# RECEPTOR_AIS_DEMOD_R00.net
KiCad netlist of a schematic drawn in Altium Designer
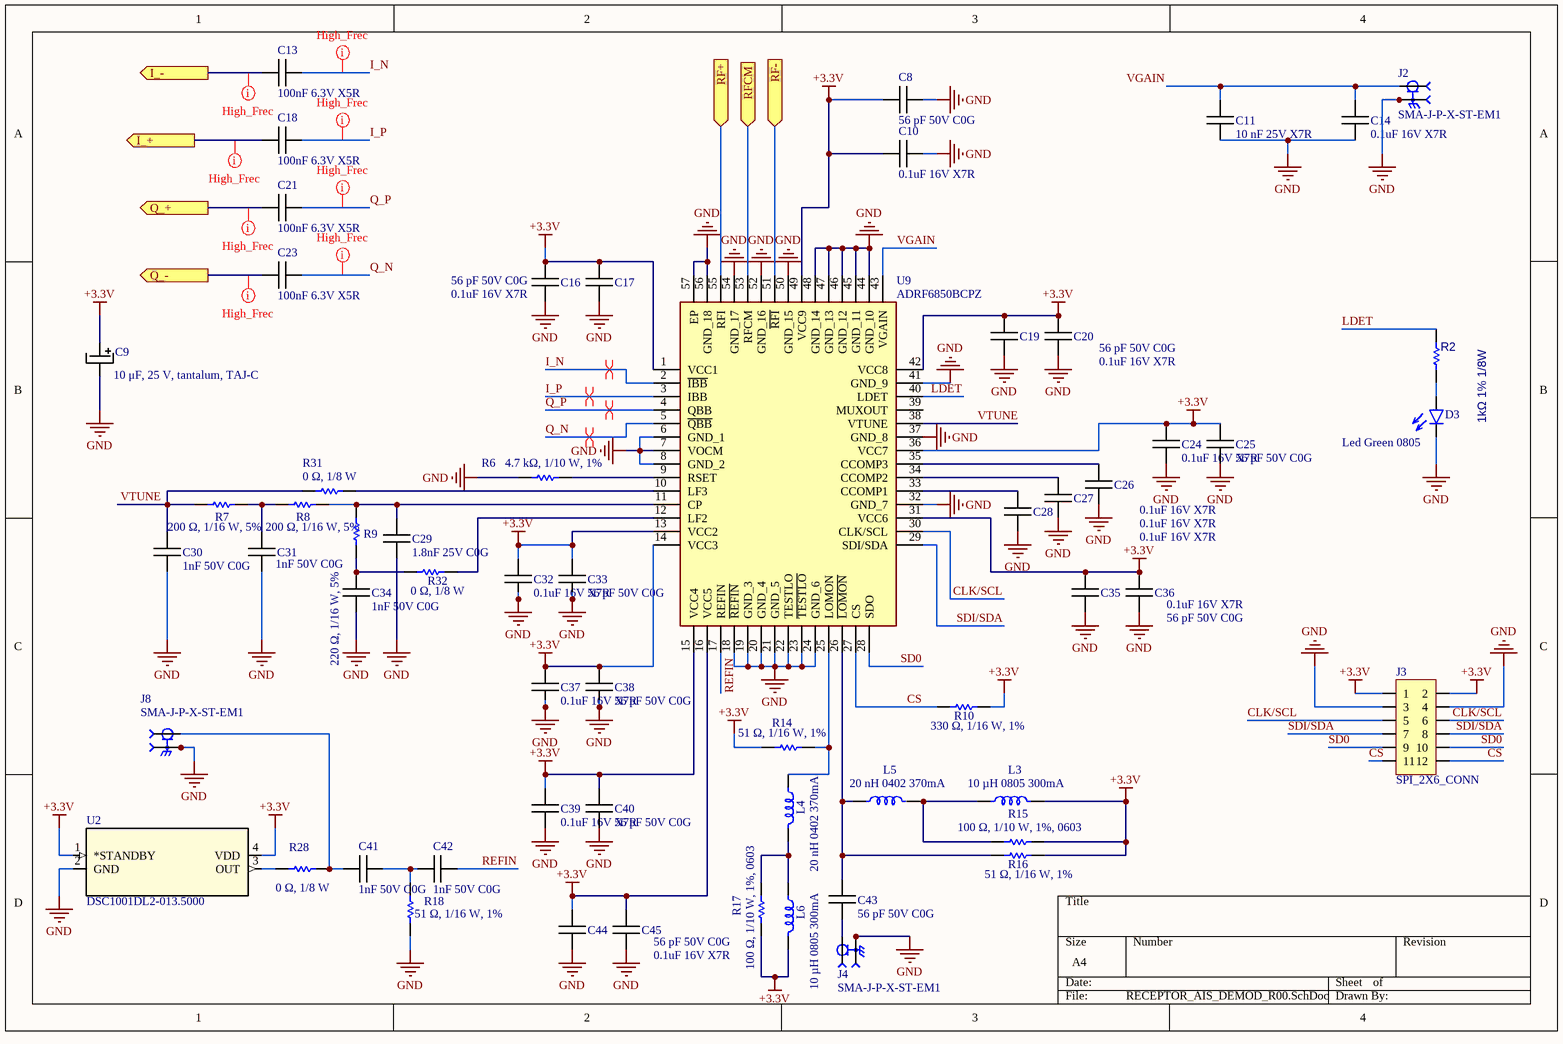
[diagram p0: RECEPTOR_AIS_DEMOD_R00.SchDoc]

(export (version "E")
  (design (tool "Eeschema 10.0.6"))
  (components
    (comp (ref "C8")
      (value "56 pF 50V C0G")
      (footprint "C_0603")
      (description "56 pF ±5% 50V Ceramic Capacitor C0G, NP0 0603 (1608 Metric)")
      (libsource (lib "RECEPTOR_AIS_R00") (part "Capacitor NP"))
    )
    (comp (ref "C9")
      (value "10 μF, 25 V, tantalum, TAJ-C")
      (footprint "TAJC_AVX-M")
      (description "10 µF Molded Tantalum Capacitors 25 V 2312 (6032 Metric) 1.8Ohm")
      (libsource (lib "RECEPTOR_AIS_R00") (part "Capacitor Pol"))
    )
    (comp (ref "C10")
      (value "0.1uF 16V X7R")
      (footprint "C_0603")
      (description "0.1 µF ±10% 16V Ceramic Capacitor X7R 0603 (1608 Metric)")
      (libsource (lib "RECEPTOR_AIS_R00") (part "Capacitor NP"))
    )
    (comp (ref "C11")
      (value "10 nF 25V X7R")
      (footprint "C_0603")
      (description "10000 pF ±10% 25V Ceramic Capacitor X7R 0603 (1608 Metric)")
      (libsource (lib "RECEPTOR_AIS_R00") (part "Capacitor NP"))
    )
    (comp (ref "C13")
      (value "100nF 6.3V X5R")
      (footprint "C_0603")
      (description "0.1 µF ±10% 6.3V Ceramic Capacitor X5R 0603 (1608 Metric)")
      (libsource (lib "RECEPTOR_AIS_R00") (part "Capacitor NP"))
    )
    (comp (ref "C14")
      (value "0.1uF 16V X7R")
      (footprint "C_0603")
      (description "0.1 µF ±10% 16V Ceramic Capacitor X7R 0603 (1608 Metric)")
      (libsource (lib "RECEPTOR_AIS_R00") (part "Capacitor NP"))
    )
    (comp (ref "C16")
      (value "0.1uF 16V X7R")
      (footprint "C_0603")
      (description "0.1 µF ±10% 16V Ceramic Capacitor X7R 0603 (1608 Metric)")
      (libsource (lib "RECEPTOR_AIS_R00") (part "Capacitor NP"))
    )
    (comp (ref "C17")
      (value "56 pF 50V C0G")
      (footprint "C_0603")
      (description "56 pF ±5% 50V Ceramic Capacitor C0G, NP0 0603 (1608 Metric)")
      (libsource (lib "RECEPTOR_AIS_R00") (part "Capacitor NP"))
    )
    (comp (ref "C18")
      (value "100nF 6.3V X5R")
      (footprint "C_0603")
      (description "0.1 µF ±10% 6.3V Ceramic Capacitor X5R 0603 (1608 Metric)")
      (libsource (lib "RECEPTOR_AIS_R00") (part "Capacitor NP"))
    )
    (comp (ref "C19")
      (value "0.1uF 16V X7R")
      (footprint "C_0603")
      (description "0.1 µF ±10% 16V Ceramic Capacitor X7R 0603 (1608 Metric)")
      (libsource (lib "RECEPTOR_AIS_R00") (part "Capacitor NP"))
    )
    (comp (ref "C20")
      (value "56 pF 50V C0G")
      (footprint "C_0603")
      (description "56 pF ±5% 50V Ceramic Capacitor C0G, NP0 0603 (1608 Metric)")
      (libsource (lib "RECEPTOR_AIS_R00") (part "Capacitor NP"))
    )
    (comp (ref "C21")
      (value "100nF 6.3V X5R")
      (footprint "C_0603")
      (description "0.1 µF ±10% 6.3V Ceramic Capacitor X5R 0603 (1608 Metric)")
      (libsource (lib "RECEPTOR_AIS_R00") (part "Capacitor NP"))
    )
    (comp (ref "C23")
      (value "100nF 6.3V X5R")
      (footprint "C_0603")
      (description "0.1 µF ±10% 6.3V Ceramic Capacitor X5R 0603 (1608 Metric)")
      (libsource (lib "RECEPTOR_AIS_R00") (part "Capacitor NP"))
    )
    (comp (ref "C24")
      (value "0.1uF 16V X7R")
      (footprint "C_0603")
      (description "0.1 µF ±10% 16V Ceramic Capacitor X7R 0603 (1608 Metric)")
      (libsource (lib "RECEPTOR_AIS_R00") (part "Capacitor NP"))
    )
    (comp (ref "C25")
      (value "56 pF 50V C0G")
      (footprint "C_0603")
      (description "56 pF ±5% 50V Ceramic Capacitor C0G, NP0 0603 (1608 Metric)")
      (libsource (lib "RECEPTOR_AIS_R00") (part "Capacitor NP"))
    )
    (comp (ref "C26")
      (value "0.1uF 16V X7R")
      (footprint "C_0603")
      (description "0.1 µF ±10% 16V Ceramic Capacitor X7R 0603 (1608 Metric)")
      (libsource (lib "RECEPTOR_AIS_R00") (part "Capacitor NP"))
    )
    (comp (ref "C27")
      (value "0.1uF 16V X7R")
      (footprint "C_0603")
      (description "0.1 µF ±10% 16V Ceramic Capacitor X7R 0603 (1608 Metric)")
      (libsource (lib "RECEPTOR_AIS_R00") (part "Capacitor NP"))
    )
    (comp (ref "C28")
      (value "0.1uF 16V X7R")
      (footprint "C_0603")
      (description "0.1 µF ±10% 16V Ceramic Capacitor X7R 0603 (1608 Metric)")
      (libsource (lib "RECEPTOR_AIS_R00") (part "Capacitor NP"))
    )
    (comp (ref "C29")
      (value "1.8nF 25V C0G")
      (footprint "C_0603")
      (description "1800 pF ±5% 25V Ceramic Capacitor C0G, NP0 0603 (1608 Metric)")
      (libsource (lib "RECEPTOR_AIS_R00") (part "Capacitor NP"))
    )
    (comp (ref "C30")
      (value "1nF 50V C0G")
      (footprint "C_0603")
      (description "1000 pF ±5% 50V Ceramic Capacitor C0G, NP0 0603 (1608 Metric)")
      (libsource (lib "RECEPTOR_AIS_R00") (part "Capacitor NP"))
    )
    (comp (ref "C31")
      (value "1nF 50V C0G")
      (footprint "C_0603")
      (description "1000 pF ±5% 50V Ceramic Capacitor C0G, NP0 0603 (1608 Metric)")
      (libsource (lib "RECEPTOR_AIS_R00") (part "Capacitor NP"))
    )
    (comp (ref "C32")
      (value "0.1uF 16V X7R")
      (footprint "C_0603")
      (description "0.1 µF ±10% 16V Ceramic Capacitor X7R 0603 (1608 Metric)")
      (libsource (lib "RECEPTOR_AIS_R00") (part "Capacitor NP"))
    )
    (comp (ref "C33")
      (value "56 pF 50V C0G")
      (footprint "C_0603")
      (description "56 pF ±5% 50V Ceramic Capacitor C0G, NP0 0603 (1608 Metric)")
      (libsource (lib "RECEPTOR_AIS_R00") (part "Capacitor NP"))
    )
    (comp (ref "C34")
      (value "1nF 50V C0G")
      (footprint "C_0603")
      (description "1000 pF ±5% 50V Ceramic Capacitor C0G, NP0 0603 (1608 Metric)")
      (libsource (lib "RECEPTOR_AIS_R00") (part "Capacitor NP"))
    )
    (comp (ref "C35")
      (value "0.1uF 16V X7R")
      (footprint "C_0603")
      (description "0.1 µF ±10% 16V Ceramic Capacitor X7R 0603 (1608 Metric)")
      (libsource (lib "RECEPTOR_AIS_R00") (part "Capacitor NP"))
    )
    (comp (ref "C36")
      (value "56 pF 50V C0G")
      (footprint "C_0603")
      (description "56 pF ±5% 50V Ceramic Capacitor C0G, NP0 0603 (1608 Metric)")
      (libsource (lib "RECEPTOR_AIS_R00") (part "Capacitor NP"))
    )
    (comp (ref "C37")
      (value "0.1uF 16V X7R")
      (footprint "C_0603")
      (description "0.1 µF ±10% 16V Ceramic Capacitor X7R 0603 (1608 Metric)")
      (libsource (lib "RECEPTOR_AIS_R00") (part "Capacitor NP"))
    )
    (comp (ref "C38")
      (value "56 pF 50V C0G")
      (footprint "C_0603")
      (description "56 pF ±5% 50V Ceramic Capacitor C0G, NP0 0603 (1608 Metric)")
      (libsource (lib "RECEPTOR_AIS_R00") (part "Capacitor NP"))
    )
    (comp (ref "C39")
      (value "0.1uF 16V X7R")
      (footprint "C_0603")
      (description "0.1 µF ±10% 16V Ceramic Capacitor X7R 0603 (1608 Metric)")
      (libsource (lib "RECEPTOR_AIS_R00") (part "Capacitor NP"))
    )
    (comp (ref "C40")
      (value "56 pF 50V C0G")
      (footprint "C_0603")
      (description "56 pF ±5% 50V Ceramic Capacitor C0G, NP0 0603 (1608 Metric)")
      (libsource (lib "RECEPTOR_AIS_R00") (part "Capacitor NP"))
    )
    (comp (ref "C41")
      (value "1nF 50V C0G")
      (footprint "C_0603")
      (description "1000 pF ±5% 50V Ceramic Capacitor C0G, NP0 0603 (1608 Metric)")
      (libsource (lib "RECEPTOR_AIS_R00") (part "Capacitor NP"))
    )
    (comp (ref "C42")
      (value "1nF 50V C0G")
      (footprint "C_0603")
      (description "1000 pF ±5% 50V Ceramic Capacitor C0G, NP0 0603 (1608 Metric)")
      (libsource (lib "RECEPTOR_AIS_R00") (part "Capacitor NP"))
    )
    (comp (ref "C43")
      (value "56 pF 50V C0G")
      (footprint "C_0603")
      (description "56 pF ±5% 50V Ceramic Capacitor C0G, NP0 0603 (1608 Metric)")
      (libsource (lib "RECEPTOR_AIS_R00") (part "Capacitor NP"))
    )
    (comp (ref "C44")
      (value "0.1uF 16V X7R")
      (footprint "C_0603")
      (description "0.1 µF ±10% 16V Ceramic Capacitor X7R 0603 (1608 Metric)")
      (libsource (lib "RECEPTOR_AIS_R00") (part "Capacitor NP"))
    )
    (comp (ref "C45")
      (value "56 pF 50V C0G")
      (footprint "C_0603")
      (description "56 pF ±5% 50V Ceramic Capacitor C0G, NP0 0603 (1608 Metric)")
      (libsource (lib "RECEPTOR_AIS_R00") (part "Capacitor NP"))
    )
    (comp (ref "D3")
      (value "Led Green 0805")
      (footprint "LED_0805")
      (description "Green 569nm LED Indication - Discrete 2.1V 0805 (2012 Metric)")
      (libsource (lib "RECEPTOR_AIS_R00") (part "Led"))
    )
    (comp (ref "J2")
      (value "SMA-J-P-X-ST-EM1")
      (footprint "CONN_SMA-J-P-H-ST-EM1_SAI")
      (description "SMA Connector Jack, Female Socket 50 Ohms Board Edge, Cutout; Surface Mount Solder")
      (fields (field (name "MF") "Samtec") (field (name "MP") "SMA-J-P-H-ST-EM3"))
      (libsource (lib "RECEPTOR_AIS_R00") (part "SMA-J-P-X-ST-EM1"))
    )
    (comp (ref "J3")
      (value "SPI_2X6_CONN")
      (footprint "Pin_Header_2x6")
      (libsource (lib "RECEPTOR_AIS_R00") (part "SPI_2x6Pin_Connection"))
    )
    (comp (ref "J4")
      (value "SMA-J-P-X-ST-EM1")
      (footprint "CONN_SMA-J-P-H-ST-EM1_SAI")
      (description "SMA Connector Jack, Female Socket 50 Ohms Board Edge, Cutout; Surface Mount Solder")
      (fields (field (name "MF") "Samtec") (field (name "MP") "SMA-J-P-H-ST-EM3"))
      (libsource (lib "RECEPTOR_AIS_R00") (part "SMA-J-P-X-ST-EM1"))
    )
    (comp (ref "J8")
      (value "SMA-J-P-X-ST-EM1")
      (footprint "CONN_SMA-J-P-H-ST-EM1_SAI")
      (description "SMA Connector Jack, Female Socket 50 Ohms Board Edge, Cutout; Surface Mount Solder")
      (fields (field (name "MF") "Samtec") (field (name "MP") "SMA-J-P-H-ST-EM3"))
      (libsource (lib "RECEPTOR_AIS_R00") (part "SMA-J-P-X-ST-EM1"))
    )
    (comp (ref "L3")
      (value "10 µH 0805 300mA")
      (footprint "L_0603")
      (description "LQM18DN100M70L - 10 µH Shielded Multilayer Inductor 300 mA 1.365Ohm Max 0603 (1608 Metric)")
      (libsource (lib "RECEPTOR_AIS_R00") (part "IND"))
    )
    (comp (ref "L4")
      (value "20 nH 0402 370mA")
      (footprint "L_0402")
      (description "LQW15AN20NJ00D - 20 nH Unshielded Wirewound Inductor 370 mA 270mOhm Max 0402 (1005 Metric)")
      (libsource (lib "RECEPTOR_AIS_R00") (part "IND"))
    )
    (comp (ref "L5")
      (value "20 nH 0402 370mA")
      (footprint "L_0402")
      (description "LQW15AN20NJ00D - 20 nH Unshielded Wirewound Inductor 370 mA 270mOhm Max 0402 (1005 Metric)")
      (libsource (lib "RECEPTOR_AIS_R00") (part "IND"))
    )
    (comp (ref "L6")
      (value "10 µH 0805 300mA")
      (footprint "L_0603")
      (description "LQM18DN100M70L - 10 µH Shielded Multilayer Inductor 300 mA 1.365Ohm Max 0603 (1608 Metric)")
      (libsource (lib "RECEPTOR_AIS_R00") (part "IND"))
    )
    (comp (ref "R2")
      (value "1kΩ 1% 1/8W")
      (footprint "R_0603")
      (description "100 Ohms ±0.1% 1/8W Chip Resistor 0603 (1608 Metric) Thin Film")
      (libsource (lib "RECEPTOR_AIS_R00") (part "Res1"))
    )
    (comp (ref "R6")
      (value "4.7 kΩ, 1/10 W, 1%")
      (footprint "R_0603")
      (description "4.7 kOhms ±1% 0.1W, 1/10W Chip Resistor 0603 (1608 Metric) Moisture Resistant Thick Film")
      (libsource (lib "RECEPTOR_AIS_R00") (part "Res1"))
    )
    (comp (ref "R7")
      (value "200 Ω, 1/16 W, 5%")
      (footprint "R_0603")
      (description "200 Ohms ±5% 0.1W, 1/10W Chip Resistor 0603 (1608 Metric) Moisture Resistant Thick Film")
      (libsource (lib "RECEPTOR_AIS_R00") (part "Res1"))
    )
    (comp (ref "R8")
      (value "200 Ω, 1/16 W, 5%")
      (footprint "R_0603")
      (description "200 Ohms ±5% 0.1W, 1/10W Chip Resistor 0603 (1608 Metric) Moisture Resistant Thick Film")
      (libsource (lib "RECEPTOR_AIS_R00") (part "Res1"))
    )
    (comp (ref "R9")
      (value "220 Ω, 1/16 W, 5%")
      (footprint "R_0603")
      (description "220 Ohms ±5% 0.1W, 1/10W Chip Resistor 0603 (1608 Metric) Moisture Resistant Thick Film")
      (libsource (lib "RECEPTOR_AIS_R00") (part "Res1"))
    )
    (comp (ref "R10")
      (value "330 Ω, 1/16 W, 1%")
      (footprint "R_0805")
      (description "330 Ohms ±1% 0.125W, 1/8W Chip Resistor 0805 (2012 Metric) Moisture Resistant Thick Film")
      (libsource (lib "RECEPTOR_AIS_R00") (part "Res1"))
    )
    (comp (ref "R14")
      (value "51 Ω, 1/16 W, 1%")
      (footprint "R_0805")
      (libsource (lib "RECEPTOR_AIS_R00") (part "Res1"))
    )
    (comp (ref "R15")
      (value "100 Ω, 1/10 W, 1%, 0603")
      (footprint "R_0603")
      (description "100 Ohms ±1% 0.1W, 1/10W Chip Resistor 0603 (1608 Metric) Moisture Resistant Thick Film")
      (libsource (lib "RECEPTOR_AIS_R00") (part "Res1"))
    )
    (comp (ref "R16")
      (value "51 Ω, 1/16 W, 1%")
      (footprint "R_0805")
      (libsource (lib "RECEPTOR_AIS_R00") (part "Res1"))
    )
    (comp (ref "R17")
      (value "100 Ω, 1/10 W, 1%, 0603")
      (footprint "R_0603")
      (description "100 Ohms ±1% 0.1W, 1/10W Chip Resistor 0603 (1608 Metric) Moisture Resistant Thick Film")
      (libsource (lib "RECEPTOR_AIS_R00") (part "Res1"))
    )
    (comp (ref "R18")
      (value "51 Ω, 1/16 W, 1%")
      (footprint "R_0805")
      (libsource (lib "RECEPTOR_AIS_R00") (part "Res1"))
    )
    (comp (ref "R28")
      (value "0 Ω, 1/8 W")
      (footprint "R_0603")
      (libsource (lib "RECEPTOR_AIS_R00") (part "Res1"))
    )
    (comp (ref "R31")
      (value "0 Ω, 1/8 W")
      (footprint "R_0603")
      (libsource (lib "RECEPTOR_AIS_R00") (part "Res1"))
    )
    (comp (ref "R32")
      (value "0 Ω, 1/8 W")
      (footprint "R_0603")
      (libsource (lib "RECEPTOR_AIS_R00") (part "Res1"))
    )
    (comp (ref "U2")
      (value "DSC1001DL2-013.5000")
      (footprint "CDFN4_2P5X2_MCH")
      (description "13.5 MHz XO (Standard) CMOS Oscillator 1.7V ~ 3.6V Standby (Power Down) 4-VDFN")
      (fields (field (name "COPYRIGHT") "Copyright (C) 2026 Ultra Librarian. All rights reserved."))
      (libsource (lib "RECEPTOR_AIS_R00") (part "DSC1001DL2-013.5000"))
    )
    (comp (ref "U9")
      (value "ADRF6850BCPZ")
      (footprint "QFN50P800X800X100-57N-D")
      (description "ADRF6850BCPZ, Demodulator Quadrature 250MHz 3.15  3.45 V 56-Pin LFCSP VQ")
      (fields (field (name "MOUSER PART NUMBER") "584-ADRF6850BCPZ"))
      (libsource (lib "RECEPTOR_AIS_R00") (part "ADRF6850BCPZ"))
    )
  )
  (nets
    (net (code "1") (name "+3.3V") (class "Default")
      (node (ref "C10") (pin "1") (pinfunction "1_1") (pintype "passive"))
      (node (ref "C16") (pin "1") (pinfunction "1_1") (pintype "passive"))
      (node (ref "C17") (pin "1") (pinfunction "1_1") (pintype "passive"))
      (node (ref "C19") (pin "1") (pinfunction "1_1") (pintype "passive"))
      (node (ref "C20") (pin "1") (pinfunction "1_1") (pintype "passive"))
      (node (ref "C24") (pin "1") (pinfunction "1_1") (pintype "passive"))
      (node (ref "C25") (pin "1") (pinfunction "1_1") (pintype "passive"))
      (node (ref "C32") (pin "1") (pinfunction "1_1") (pintype "passive"))
      (node (ref "C33") (pin "1") (pinfunction "1_1") (pintype "passive"))
      (node (ref "C35") (pin "1") (pinfunction "1_1") (pintype "passive"))
      (node (ref "C36") (pin "1") (pinfunction "1_1") (pintype "passive"))
      (node (ref "C37") (pin "1") (pinfunction "1_1") (pintype "passive"))
      (node (ref "C38") (pin "1") (pinfunction "1_1") (pintype "passive"))
      (node (ref "C39") (pin "1") (pinfunction "1_1") (pintype "passive"))
      (node (ref "C40") (pin "1") (pinfunction "1_1") (pintype "passive"))
      (node (ref "C44") (pin "1") (pinfunction "1_1") (pintype "passive"))
      (node (ref "C45") (pin "1") (pinfunction "1_1") (pintype "passive"))
      (node (ref "C8") (pin "1") (pinfunction "1_1") (pintype "passive"))
      (node (ref "C9") (pin "1") (pinfunction "1_1") (pintype "power_in"))
      (node (ref "J3") (pin "1") (pinfunction "1_1") (pintype "passive"))
      (node (ref "J3") (pin "2") (pinfunction "2_2") (pintype "passive"))
      (node (ref "L3") (pin "2") (pinfunction "2_2") (pintype "passive"))
      (node (ref "L6") (pin "2") (pinfunction "2_2") (pintype "passive"))
      (node (ref "R10") (pin "2") (pinfunction "2_2") (pintype "passive"))
      (node (ref "R14") (pin "2") (pinfunction "2_2") (pintype "passive"))
      (node (ref "R15") (pin "2") (pinfunction "2_2") (pintype "passive"))
      (node (ref "R16") (pin "2") (pinfunction "2_2") (pintype "passive"))
      (node (ref "R17") (pin "2") (pinfunction "2_2") (pintype "passive"))
      (node (ref "U2") (pin "1") (pinfunction "*STANDBY_1") (pintype "input"))
      (node (ref "U2") (pin "4") (pinfunction "VDD_4") (pintype "power_in"))
      (node (ref "U9") (pin "1") (pinfunction "VCC1_1") (pintype "passive"))
      (node (ref "U9") (pin "13") (pinfunction "VCC2_13") (pintype "passive"))
      (node (ref "U9") (pin "14") (pinfunction "VCC3_14") (pintype "passive"))
      (node (ref "U9") (pin "15") (pinfunction "VCC4_15") (pintype "passive"))
      (node (ref "U9") (pin "16") (pinfunction "VCC5_16") (pintype "passive"))
      (node (ref "U9") (pin "31") (pinfunction "VCC6_31") (pintype "passive"))
      (node (ref "U9") (pin "36") (pinfunction "VCC7_36") (pintype "passive"))
      (node (ref "U9") (pin "42") (pinfunction "VCC8_42") (pintype "passive"))
      (node (ref "U9") (pin "49") (pinfunction "VCC9_49") (pintype "passive"))
    )
    (net (code "2") (name "/CLK{slash}SCL") (class "Default")
      (node (ref "J3") (pin "5") (pinfunction "5_5") (pintype "passive"))
      (node (ref "J3") (pin "6") (pinfunction "6_6") (pintype "passive"))
      (node (ref "U9") (pin "30") (pinfunction "CLK/SCL_30") (pintype "passive"))
    )
    (net (code "3") (name "/CS") (class "Default")
      (node (ref "J3") (pin "11") (pinfunction "11_11") (pintype "power_in"))
      (node (ref "J3") (pin "12") (pinfunction "12_12") (pintype "power_in"))
      (node (ref "R10") (pin "1") (pinfunction "1_1") (pintype "passive"))
      (node (ref "U9") (pin "27") (pinfunction "CS_27") (pintype "passive"))
    )
    (net (code "4") (name "/I_+") (class "Default")
      (node (ref "C18") (pin "2") (pinfunction "2_2") (pintype "passive"))
    )
    (net (code "5") (name "/I_-") (class "Default")
      (node (ref "C13") (pin "2") (pinfunction "2_2") (pintype "passive"))
    )
    (net (code "6") (name "/I_N") (class "Default")
      (node (ref "C13") (pin "1") (pinfunction "1_1") (pintype "passive"))
      (node (ref "U9") (pin "2") (pinfunction "~{IBB}_2") (pintype "passive"))
    )
    (net (code "7") (name "/I_P") (class "Default")
      (node (ref "C18") (pin "1") (pinfunction "1_1") (pintype "passive"))
      (node (ref "U9") (pin "3") (pinfunction "IBB_3") (pintype "passive"))
    )
    (net (code "8") (name "/LDET") (class "Default")
      (node (ref "R2") (pin "2") (pinfunction "2_2") (pintype "passive"))
      (node (ref "U9") (pin "40") (pinfunction "LDET_40") (pintype "passive"))
    )
    (net (code "9") (name "/Q_+") (class "Default")
      (node (ref "C21") (pin "2") (pinfunction "2_2") (pintype "passive"))
    )
    (net (code "10") (name "/Q_-") (class "Default")
      (node (ref "C23") (pin "2") (pinfunction "2_2") (pintype "passive"))
    )
    (net (code "11") (name "/Q_N") (class "Default")
      (node (ref "C23") (pin "1") (pinfunction "1_1") (pintype "passive"))
      (node (ref "U9") (pin "5") (pinfunction "~{QBB}_5") (pintype "passive"))
    )
    (net (code "12") (name "/Q_P") (class "Default")
      (node (ref "C21") (pin "1") (pinfunction "1_1") (pintype "passive"))
      (node (ref "U9") (pin "4") (pinfunction "QBB_4") (pintype "passive"))
    )
    (net (code "13") (name "/REFIN") (class "Default")
      (node (ref "C42") (pin "1") (pinfunction "1_1") (pintype "passive"))
      (node (ref "U9") (pin "17") (pinfunction "REFIN_17") (pintype "passive"))
    )
    (net (code "14") (name "/RF+") (class "Default")
      (node (ref "U9") (pin "55") (pinfunction "RFI_55") (pintype "passive"))
    )
    (net (code "15") (name "/RF-") (class "Default")
      (node (ref "U9") (pin "51") (pinfunction "~{RFI}_51") (pintype "passive"))
    )
    (net (code "16") (name "/RFCM") (class "Default")
      (node (ref "U9") (pin "53") (pinfunction "RFCM_53") (pintype "passive"))
    )
    (net (code "17") (name "/SD0") (class "Default")
      (node (ref "J3") (pin "10") (pinfunction "10_10") (pintype "power_in"))
      (node (ref "J3") (pin "9") (pinfunction "9_9") (pintype "power_in"))
      (node (ref "U9") (pin "28") (pinfunction "SDO_28") (pintype "passive"))
    )
    (net (code "18") (name "/SDI{slash}SDA") (class "Default")
      (node (ref "J3") (pin "7") (pinfunction "7_7") (pintype "power_in"))
      (node (ref "J3") (pin "8") (pinfunction "8_8") (pintype "power_in"))
      (node (ref "U9") (pin "29") (pinfunction "SDI/SDA_29") (pintype "passive"))
    )
    (net (code "19") (name "/VGAIN") (class "Default")
      (node (ref "C11") (pin "1") (pinfunction "1_1") (pintype "passive"))
      (node (ref "C14") (pin "1") (pinfunction "1_1") (pintype "passive"))
      (node (ref "J2") (pin "1") (pinfunction "1_1") (pintype "passive"))
      (node (ref "U9") (pin "43") (pinfunction "VGAIN_43") (pintype "passive"))
    )
    (net (code "20") (name "/VTUNE") (class "Default")
      (node (ref "C30") (pin "1") (pinfunction "1_1") (pintype "passive"))
      (node (ref "R31") (pin "1") (pinfunction "1_1") (pintype "passive"))
      (node (ref "R7") (pin "2") (pinfunction "2_2") (pintype "passive"))
      (node (ref "U9") (pin "38") (pinfunction "VTUNE_38") (pintype "passive"))
    )
    (net (code "21") (name "GND") (class "Default")
      (node (ref "C10") (pin "2") (pinfunction "2_2") (pintype "passive"))
      (node (ref "C11") (pin "2") (pinfunction "2_2") (pintype "passive"))
      (node (ref "C14") (pin "2") (pinfunction "2_2") (pintype "passive"))
      (node (ref "C16") (pin "2") (pinfunction "2_2") (pintype "passive"))
      (node (ref "C17") (pin "2") (pinfunction "2_2") (pintype "passive"))
      (node (ref "C19") (pin "2") (pinfunction "2_2") (pintype "passive"))
      (node (ref "C20") (pin "2") (pinfunction "2_2") (pintype "passive"))
      (node (ref "C24") (pin "2") (pinfunction "2_2") (pintype "passive"))
      (node (ref "C25") (pin "2") (pinfunction "2_2") (pintype "passive"))
      (node (ref "C26") (pin "2") (pinfunction "2_2") (pintype "passive"))
      (node (ref "C27") (pin "2") (pinfunction "2_2") (pintype "passive"))
      (node (ref "C28") (pin "2") (pinfunction "2_2") (pintype "passive"))
      (node (ref "C29") (pin "2") (pinfunction "2_2") (pintype "passive"))
      (node (ref "C30") (pin "2") (pinfunction "2_2") (pintype "passive"))
      (node (ref "C31") (pin "2") (pinfunction "2_2") (pintype "passive"))
      (node (ref "C32") (pin "2") (pinfunction "2_2") (pintype "passive"))
      (node (ref "C33") (pin "2") (pinfunction "2_2") (pintype "passive"))
      (node (ref "C34") (pin "2") (pinfunction "2_2") (pintype "passive"))
      (node (ref "C35") (pin "2") (pinfunction "2_2") (pintype "passive"))
      (node (ref "C36") (pin "2") (pinfunction "2_2") (pintype "passive"))
      (node (ref "C37") (pin "2") (pinfunction "2_2") (pintype "passive"))
      (node (ref "C38") (pin "2") (pinfunction "2_2") (pintype "passive"))
      (node (ref "C39") (pin "2") (pinfunction "2_2") (pintype "passive"))
      (node (ref "C40") (pin "2") (pinfunction "2_2") (pintype "passive"))
      (node (ref "C44") (pin "2") (pinfunction "2_2") (pintype "passive"))
      (node (ref "C45") (pin "2") (pinfunction "2_2") (pintype "passive"))
      (node (ref "C8") (pin "2") (pinfunction "2_2") (pintype "passive"))
      (node (ref "C9") (pin "2") (pinfunction "2_2") (pintype "power_in"))
      (node (ref "D3") (pin "2") (pinfunction "K_2") (pintype "power_in"))
      (node (ref "J2") (pin "2") (pinfunction "2_2") (pintype "passive"))
      (node (ref "J2") (pin "3") (pinfunction "2_3") (pintype "passive"))
      (node (ref "J3") (pin "3") (pinfunction "3_3") (pintype "passive"))
      (node (ref "J3") (pin "4") (pinfunction "4_4") (pintype "passive"))
      (node (ref "J4") (pin "2") (pinfunction "2_2") (pintype "passive"))
      (node (ref "J4") (pin "3") (pinfunction "2_3") (pintype "passive"))
      (node (ref "J8") (pin "2") (pinfunction "2_2") (pintype "passive"))
      (node (ref "J8") (pin "3") (pinfunction "2_3") (pintype "passive"))
      (node (ref "R18") (pin "2") (pinfunction "2_2") (pintype "passive"))
      (node (ref "R6") (pin "2") (pinfunction "2_2") (pintype "passive"))
      (node (ref "U2") (pin "2") (pinfunction "GND_2") (pintype "power_in"))
      (node (ref "U9") (pin "18") (pinfunction "~{REFIN}_18") (pintype "passive"))
      (node (ref "U9") (pin "19") (pinfunction "GND_3_19") (pintype "passive"))
      (node (ref "U9") (pin "20") (pinfunction "GND_4_20") (pintype "passive"))
      (node (ref "U9") (pin "21") (pinfunction "GND_5_21") (pintype "passive"))
      (node (ref "U9") (pin "22") (pinfunction "TESTLO_22") (pintype "passive"))
      (node (ref "U9") (pin "23") (pinfunction "~{TESTLO}_23") (pintype "passive"))
      (node (ref "U9") (pin "24") (pinfunction "GND_6_24") (pintype "passive"))
      (node (ref "U9") (pin "32") (pinfunction "GND_7_32") (pintype "passive"))
      (node (ref "U9") (pin "37") (pinfunction "GND_8_37") (pintype "passive"))
      (node (ref "U9") (pin "41") (pinfunction "GND_9_41") (pintype "passive"))
      (node (ref "U9") (pin "44") (pinfunction "GND_10_44") (pintype "passive"))
      (node (ref "U9") (pin "45") (pinfunction "GND_11_45") (pintype "passive"))
      (node (ref "U9") (pin "46") (pinfunction "GND_12_46") (pintype "passive"))
      (node (ref "U9") (pin "47") (pinfunction "GND_13_47") (pintype "passive"))
      (node (ref "U9") (pin "48") (pinfunction "GND_14_48") (pintype "passive"))
      (node (ref "U9") (pin "50") (pinfunction "GND_15_50") (pintype "passive"))
      (node (ref "U9") (pin "52") (pinfunction "GND_16_52") (pintype "passive"))
      (node (ref "U9") (pin "54") (pinfunction "GND_17_54") (pintype "passive"))
      (node (ref "U9") (pin "56") (pinfunction "GND_18_56") (pintype "passive"))
      (node (ref "U9") (pin "57") (pinfunction "EP_57") (pintype "passive"))
      (node (ref "U9") (pin "6") (pinfunction "GND_1_6") (pintype "passive"))
      (node (ref "U9") (pin "7") (pinfunction "VOCM_7") (pintype "passive"))
      (node (ref "U9") (pin "8") (pinfunction "GND_2_8") (pintype "passive"))
    )
    (net (code "22") (name "Net-(C31-Pad1)") (class "Default")
      (node (ref "C31") (pin "1") (pinfunction "1_1") (pintype "passive"))
      (node (ref "R7") (pin "1") (pinfunction "1_1") (pintype "passive"))
      (node (ref "R8") (pin "2") (pinfunction "2_2") (pintype "passive"))
    )
    (net (code "23") (name "Net-(C34-Pad1)") (class "Default")
      (node (ref "C34") (pin "1") (pinfunction "1_1") (pintype "passive"))
      (node (ref "R32") (pin "1") (pinfunction "1_1") (pintype "passive"))
      (node (ref "R9") (pin "2") (pinfunction "2_2") (pintype "passive"))
    )
    (net (code "24") (name "Net-(C41-Pad1)") (class "Default")
      (node (ref "C41") (pin "1") (pinfunction "1_1") (pintype "passive"))
      (node (ref "J8") (pin "1") (pinfunction "1_1") (pintype "passive"))
      (node (ref "R28") (pin "2") (pinfunction "2_2") (pintype "passive"))
    )
    (net (code "25") (name "Net-(C41-Pad2)") (class "Default")
      (node (ref "C41") (pin "2") (pinfunction "2_2") (pintype "passive"))
      (node (ref "C42") (pin "2") (pinfunction "2_2") (pintype "passive"))
      (node (ref "R18") (pin "1") (pinfunction "1_1") (pintype "passive"))
    )
    (net (code "26") (name "Net-(C43-Pad2)") (class "Default")
      (node (ref "C43") (pin "2") (pinfunction "2_2") (pintype "passive"))
      (node (ref "J4") (pin "1") (pinfunction "1_1") (pintype "passive"))
    )
    (net (code "27") (name "Net-(D3-A)") (class "Default")
      (node (ref "D3") (pin "1") (pinfunction "A_1") (pintype "power_in"))
      (node (ref "R2") (pin "1") (pinfunction "1_1") (pintype "passive"))
    )
    (net (code "28") (name "Net-(L3-Pad1)") (class "Default")
      (node (ref "L3") (pin "1") (pinfunction "1_1") (pintype "passive"))
      (node (ref "L5") (pin "2") (pinfunction "2_2") (pintype "passive"))
      (node (ref "R15") (pin "1") (pinfunction "1_1") (pintype "passive"))
    )
    (net (code "29") (name "Net-(L4-Pad2)") (class "Default")
      (node (ref "L4") (pin "2") (pinfunction "2_2") (pintype "passive"))
      (node (ref "L6") (pin "1") (pinfunction "1_1") (pintype "passive"))
      (node (ref "R17") (pin "1") (pinfunction "1_1") (pintype "passive"))
    )
    (net (code "30") (name "Net-(U2-OUT)") (class "Default")
      (node (ref "R28") (pin "1") (pinfunction "1_1") (pintype "passive"))
      (node (ref "U2") (pin "3") (pinfunction "OUT_3") (pintype "output"))
    )
    (net (code "31") (name "Net-(U9-CCOMP1)") (class "Default")
      (node (ref "C28") (pin "1") (pinfunction "1_1") (pintype "passive"))
      (node (ref "U9") (pin "33") (pinfunction "CCOMP1_33") (pintype "passive"))
    )
    (net (code "32") (name "Net-(U9-CCOMP2)") (class "Default")
      (node (ref "C27") (pin "1") (pinfunction "1_1") (pintype "passive"))
      (node (ref "U9") (pin "34") (pinfunction "CCOMP2_34") (pintype "passive"))
    )
    (net (code "33") (name "Net-(U9-CCOMP3)") (class "Default")
      (node (ref "C26") (pin "1") (pinfunction "1_1") (pintype "passive"))
      (node (ref "U9") (pin "35") (pinfunction "CCOMP3_35") (pintype "passive"))
    )
    (net (code "34") (name "Net-(U9-CP)") (class "Default")
      (node (ref "C29") (pin "1") (pinfunction "1_1") (pintype "passive"))
      (node (ref "R8") (pin "1") (pinfunction "1_1") (pintype "passive"))
      (node (ref "R9") (pin "1") (pinfunction "1_1") (pintype "passive"))
      (node (ref "U9") (pin "11") (pinfunction "CP_11") (pintype "passive"))
    )
    (net (code "35") (name "Net-(U9-LF2)") (class "Default")
      (node (ref "R32") (pin "2") (pinfunction "2_2") (pintype "passive"))
      (node (ref "U9") (pin "12") (pinfunction "LF2_12") (pintype "passive"))
    )
    (net (code "36") (name "Net-(U9-LF3)") (class "Default")
      (node (ref "R31") (pin "2") (pinfunction "2_2") (pintype "passive"))
      (node (ref "U9") (pin "10") (pinfunction "LF3_10") (pintype "passive"))
    )
    (net (code "37") (name "Net-(U9-LOMON)") (class "Default")
      (node (ref "L4") (pin "1") (pinfunction "1_1") (pintype "passive"))
      (node (ref "R14") (pin "1") (pinfunction "1_1") (pintype "passive"))
      (node (ref "U9") (pin "25") (pinfunction "LOMON_25") (pintype "passive"))
    )
    (net (code "38") (name "Net-(U9-RSET)") (class "Default")
      (node (ref "R6") (pin "1") (pinfunction "1_1") (pintype "passive"))
      (node (ref "U9") (pin "9") (pinfunction "RSET_9") (pintype "passive"))
    )
    (net (code "39") (name "Net-(U9-~{LOMON})") (class "Default")
      (node (ref "C43") (pin "1") (pinfunction "1_1") (pintype "passive"))
      (node (ref "L5") (pin "1") (pinfunction "1_1") (pintype "passive"))
      (node (ref "R16") (pin "1") (pinfunction "1_1") (pintype "passive"))
      (node (ref "U9") (pin "26") (pinfunction "~{LOMON}_26") (pintype "passive"))
    )
    (net (code "40") (name "unconnected-(U9-MUXOUT-Pad39)") (class "Default")
      (node (ref "U9") (pin "39") (pinfunction "MUXOUT_39") (pintype "passive"))
    )
  )
)
